# untitled.net
KiCad netlist of a schematic drawn in EAGLE
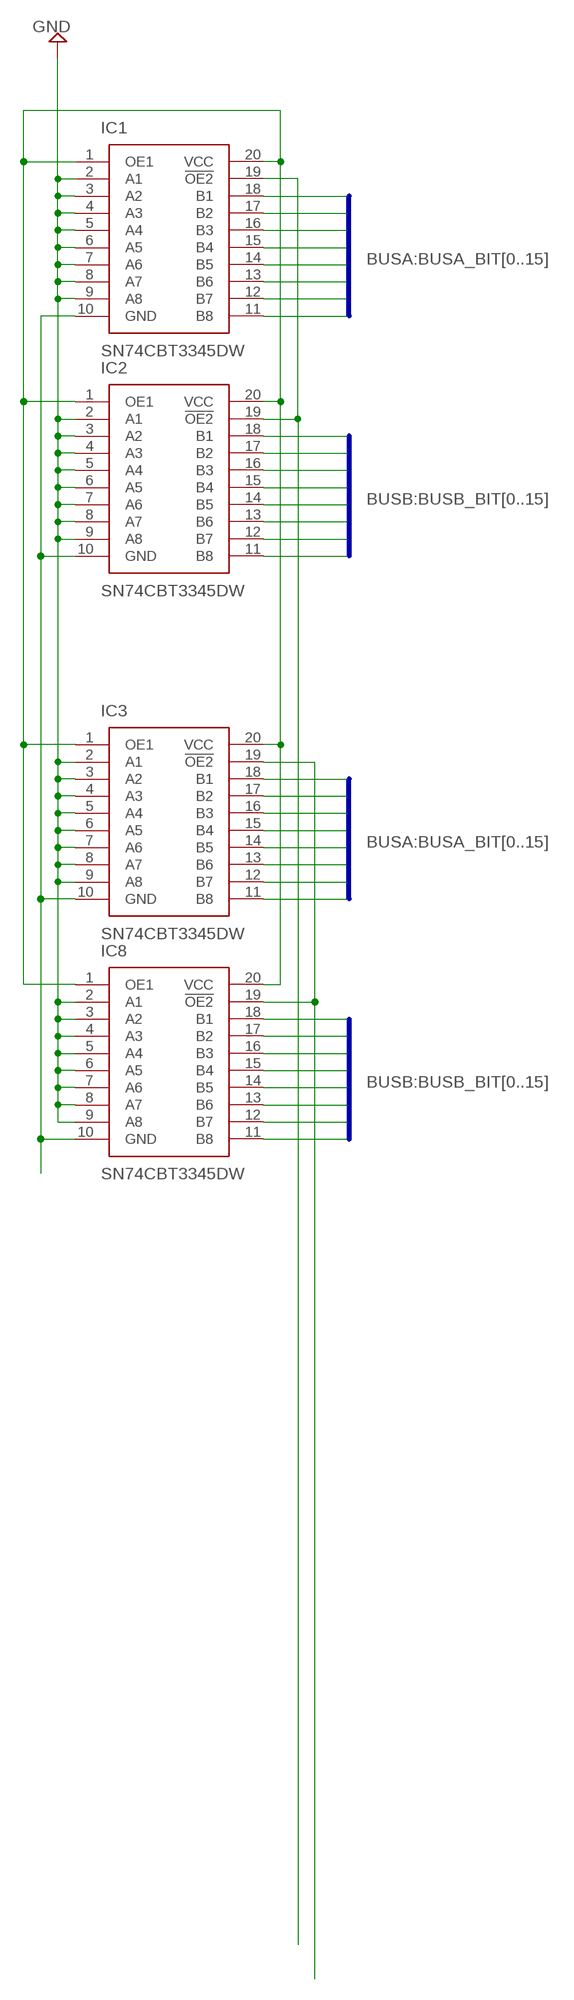
[diagram p0: schematic, sheet 1]

(export (version "E")
  (design (tool "Eeschema 10.0.6"))
  (components
    (comp (ref "IC1")
      (value "SN74CBT3345DW")
      (footprint "eagle-import:SOIC127P1030X265-20N")
      (libsource (lib "eagle-import") (part "SN74CBT3345DW"))
    )
    (comp (ref "IC2")
      (value "SN74CBT3345DW")
      (footprint "eagle-import:SOIC127P1030X265-20N")
      (libsource (lib "eagle-import") (part "SN74CBT3345DW"))
    )
    (comp (ref "IC3")
      (value "SN74CBT3345DW")
      (footprint "eagle-import:SOIC127P1030X265-20N")
      (libsource (lib "eagle-import") (part "SN74CBT3345DW"))
    )
    (comp (ref "IC8")
      (value "SN74CBT3345DW")
      (footprint "eagle-import:SOIC127P1030X265-20N")
      (libsource (lib "eagle-import") (part "SN74CBT3345DW"))
    )
  )
  (nets
    (net (code "35") (name "GND") (class "Default")
      (node (ref "IC1") (pin "2") (pinfunction "A1_2") (pintype "bidirectional"))
      (node (ref "IC1") (pin "3") (pinfunction "A2_3") (pintype "bidirectional"))
      (node (ref "IC1") (pin "4") (pinfunction "A3_4") (pintype "bidirectional"))
      (node (ref "IC1") (pin "5") (pinfunction "A4_5") (pintype "bidirectional"))
      (node (ref "IC1") (pin "6") (pinfunction "A5_6") (pintype "bidirectional"))
      (node (ref "IC1") (pin "7") (pinfunction "A6_7") (pintype "bidirectional"))
      (node (ref "IC1") (pin "8") (pinfunction "A7_8") (pintype "bidirectional"))
      (node (ref "IC1") (pin "9") (pinfunction "A8_9") (pintype "bidirectional"))
      (node (ref "IC2") (pin "2") (pinfunction "A1_2") (pintype "bidirectional"))
      (node (ref "IC2") (pin "3") (pinfunction "A2_3") (pintype "bidirectional"))
      (node (ref "IC2") (pin "4") (pinfunction "A3_4") (pintype "bidirectional"))
      (node (ref "IC2") (pin "5") (pinfunction "A4_5") (pintype "bidirectional"))
      (node (ref "IC2") (pin "6") (pinfunction "A5_6") (pintype "bidirectional"))
      (node (ref "IC2") (pin "7") (pinfunction "A6_7") (pintype "bidirectional"))
      (node (ref "IC2") (pin "8") (pinfunction "A7_8") (pintype "bidirectional"))
      (node (ref "IC2") (pin "9") (pinfunction "A8_9") (pintype "bidirectional"))
      (node (ref "IC3") (pin "2") (pinfunction "A1_2") (pintype "bidirectional"))
      (node (ref "IC3") (pin "3") (pinfunction "A2_3") (pintype "bidirectional"))
      (node (ref "IC3") (pin "4") (pinfunction "A3_4") (pintype "bidirectional"))
      (node (ref "IC3") (pin "5") (pinfunction "A4_5") (pintype "bidirectional"))
      (node (ref "IC3") (pin "6") (pinfunction "A5_6") (pintype "bidirectional"))
      (node (ref "IC3") (pin "7") (pinfunction "A6_7") (pintype "bidirectional"))
      (node (ref "IC3") (pin "8") (pinfunction "A7_8") (pintype "bidirectional"))
      (node (ref "IC3") (pin "9") (pinfunction "A8_9") (pintype "bidirectional"))
      (node (ref "IC8") (pin "2") (pinfunction "A1_2") (pintype "bidirectional"))
      (node (ref "IC8") (pin "3") (pinfunction "A2_3") (pintype "bidirectional"))
      (node (ref "IC8") (pin "4") (pinfunction "A3_4") (pintype "bidirectional"))
      (node (ref "IC8") (pin "5") (pinfunction "A4_5") (pintype "bidirectional"))
      (node (ref "IC8") (pin "6") (pinfunction "A5_6") (pintype "bidirectional"))
      (node (ref "IC8") (pin "7") (pinfunction "A6_7") (pintype "bidirectional"))
      (node (ref "IC8") (pin "8") (pinfunction "A7_8") (pintype "bidirectional"))
      (node (ref "IC8") (pin "9") (pinfunction "A8_9") (pintype "bidirectional"))
    )
    (net (code "36") (name "Net-(IC1-GND)") (class "Default")
      (node (ref "IC1") (pin "10") (pinfunction "GND_10") (pintype "power_in"))
      (node (ref "IC2") (pin "10") (pinfunction "GND_10") (pintype "power_in"))
      (node (ref "IC3") (pin "10") (pinfunction "GND_10") (pintype "power_in"))
      (node (ref "IC8") (pin "10") (pinfunction "GND_10") (pintype "power_in"))
    )
    (net (code "37") (name "Net-(IC1-OE1)") (class "Default")
      (node (ref "IC1") (pin "1") (pinfunction "OE1_1") (pintype "input"))
      (node (ref "IC1") (pin "20") (pinfunction "VCC_20") (pintype "power_in"))
      (node (ref "IC2") (pin "1") (pinfunction "OE1_1") (pintype "input"))
      (node (ref "IC2") (pin "20") (pinfunction "VCC_20") (pintype "power_in"))
      (node (ref "IC3") (pin "1") (pinfunction "OE1_1") (pintype "input"))
      (node (ref "IC3") (pin "20") (pinfunction "VCC_20") (pintype "power_in"))
      (node (ref "IC8") (pin "1") (pinfunction "OE1_1") (pintype "input"))
      (node (ref "IC8") (pin "20") (pinfunction "VCC_20") (pintype "power_in"))
    )
    (net (code "38") (name "Net-(IC1-~{OE2})") (class "Default")
      (node (ref "IC1") (pin "19") (pinfunction "~{OE2}_19") (pintype "input"))
      (node (ref "IC2") (pin "19") (pinfunction "~{OE2}_19") (pintype "input"))
    )
    (net (code "39") (name "Net-(IC3-~{OE2})") (class "Default")
      (node (ref "IC3") (pin "19") (pinfunction "~{OE2}_19") (pintype "input"))
      (node (ref "IC8") (pin "19") (pinfunction "~{OE2}_19") (pintype "input"))
    )
    (net (code "40") (name "unconnected-(IC1-B1-Pad18)") (class "Default")
      (node (ref "IC1") (pin "18") (pinfunction "B1_18") (pintype "bidirectional"))
    )
    (net (code "41") (name "unconnected-(IC1-B2-Pad17)") (class "Default")
      (node (ref "IC1") (pin "17") (pinfunction "B2_17") (pintype "bidirectional"))
    )
    (net (code "42") (name "unconnected-(IC1-B3-Pad16)") (class "Default")
      (node (ref "IC1") (pin "16") (pinfunction "B3_16") (pintype "bidirectional"))
    )
    (net (code "43") (name "unconnected-(IC1-B4-Pad15)") (class "Default")
      (node (ref "IC1") (pin "15") (pinfunction "B4_15") (pintype "bidirectional"))
    )
    (net (code "44") (name "unconnected-(IC1-B5-Pad14)") (class "Default")
      (node (ref "IC1") (pin "14") (pinfunction "B5_14") (pintype "bidirectional"))
    )
    (net (code "45") (name "unconnected-(IC1-B6-Pad13)") (class "Default")
      (node (ref "IC1") (pin "13") (pinfunction "B6_13") (pintype "bidirectional"))
    )
    (net (code "46") (name "unconnected-(IC1-B7-Pad12)") (class "Default")
      (node (ref "IC1") (pin "12") (pinfunction "B7_12") (pintype "bidirectional"))
    )
    (net (code "47") (name "unconnected-(IC1-B8-Pad11)") (class "Default")
      (node (ref "IC1") (pin "11") (pinfunction "B8_11") (pintype "bidirectional"))
    )
    (net (code "48") (name "unconnected-(IC2-B1-Pad18)") (class "Default")
      (node (ref "IC2") (pin "18") (pinfunction "B1_18") (pintype "bidirectional"))
    )
    (net (code "49") (name "unconnected-(IC2-B2-Pad17)") (class "Default")
      (node (ref "IC2") (pin "17") (pinfunction "B2_17") (pintype "bidirectional"))
    )
    (net (code "50") (name "unconnected-(IC2-B3-Pad16)") (class "Default")
      (node (ref "IC2") (pin "16") (pinfunction "B3_16") (pintype "bidirectional"))
    )
    (net (code "51") (name "unconnected-(IC2-B4-Pad15)") (class "Default")
      (node (ref "IC2") (pin "15") (pinfunction "B4_15") (pintype "bidirectional"))
    )
    (net (code "52") (name "unconnected-(IC2-B5-Pad14)") (class "Default")
      (node (ref "IC2") (pin "14") (pinfunction "B5_14") (pintype "bidirectional"))
    )
    (net (code "53") (name "unconnected-(IC2-B6-Pad13)") (class "Default")
      (node (ref "IC2") (pin "13") (pinfunction "B6_13") (pintype "bidirectional"))
    )
    (net (code "54") (name "unconnected-(IC2-B7-Pad12)") (class "Default")
      (node (ref "IC2") (pin "12") (pinfunction "B7_12") (pintype "bidirectional"))
    )
    (net (code "55") (name "unconnected-(IC2-B8-Pad11)") (class "Default")
      (node (ref "IC2") (pin "11") (pinfunction "B8_11") (pintype "bidirectional"))
    )
    (net (code "56") (name "unconnected-(IC3-B1-Pad18)") (class "Default")
      (node (ref "IC3") (pin "18") (pinfunction "B1_18") (pintype "bidirectional"))
    )
    (net (code "57") (name "unconnected-(IC3-B2-Pad17)") (class "Default")
      (node (ref "IC3") (pin "17") (pinfunction "B2_17") (pintype "bidirectional"))
    )
    (net (code "58") (name "unconnected-(IC3-B3-Pad16)") (class "Default")
      (node (ref "IC3") (pin "16") (pinfunction "B3_16") (pintype "bidirectional"))
    )
    (net (code "59") (name "unconnected-(IC3-B4-Pad15)") (class "Default")
      (node (ref "IC3") (pin "15") (pinfunction "B4_15") (pintype "bidirectional"))
    )
    (net (code "60") (name "unconnected-(IC3-B5-Pad14)") (class "Default")
      (node (ref "IC3") (pin "14") (pinfunction "B5_14") (pintype "bidirectional"))
    )
    (net (code "61") (name "unconnected-(IC3-B6-Pad13)") (class "Default")
      (node (ref "IC3") (pin "13") (pinfunction "B6_13") (pintype "bidirectional"))
    )
    (net (code "62") (name "unconnected-(IC3-B7-Pad12)") (class "Default")
      (node (ref "IC3") (pin "12") (pinfunction "B7_12") (pintype "bidirectional"))
    )
    (net (code "63") (name "unconnected-(IC3-B8-Pad11)") (class "Default")
      (node (ref "IC3") (pin "11") (pinfunction "B8_11") (pintype "bidirectional"))
    )
    (net (code "64") (name "unconnected-(IC8-B1-Pad18)") (class "Default")
      (node (ref "IC8") (pin "18") (pinfunction "B1_18") (pintype "bidirectional"))
    )
    (net (code "65") (name "unconnected-(IC8-B2-Pad17)") (class "Default")
      (node (ref "IC8") (pin "17") (pinfunction "B2_17") (pintype "bidirectional"))
    )
    (net (code "66") (name "unconnected-(IC8-B3-Pad16)") (class "Default")
      (node (ref "IC8") (pin "16") (pinfunction "B3_16") (pintype "bidirectional"))
    )
    (net (code "67") (name "unconnected-(IC8-B4-Pad15)") (class "Default")
      (node (ref "IC8") (pin "15") (pinfunction "B4_15") (pintype "bidirectional"))
    )
    (net (code "68") (name "unconnected-(IC8-B5-Pad14)") (class "Default")
      (node (ref "IC8") (pin "14") (pinfunction "B5_14") (pintype "bidirectional"))
    )
    (net (code "69") (name "unconnected-(IC8-B6-Pad13)") (class "Default")
      (node (ref "IC8") (pin "13") (pinfunction "B6_13") (pintype "bidirectional"))
    )
    (net (code "70") (name "unconnected-(IC8-B7-Pad12)") (class "Default")
      (node (ref "IC8") (pin "12") (pinfunction "B7_12") (pintype "bidirectional"))
    )
    (net (code "71") (name "unconnected-(IC8-B8-Pad11)") (class "Default")
      (node (ref "IC8") (pin "11") (pinfunction "B8_11") (pintype "bidirectional"))
    )
  )
)
